# PacBot_Official_Schematic_2018-2019.net
KiCad netlist of a schematic drawn in EAGLE
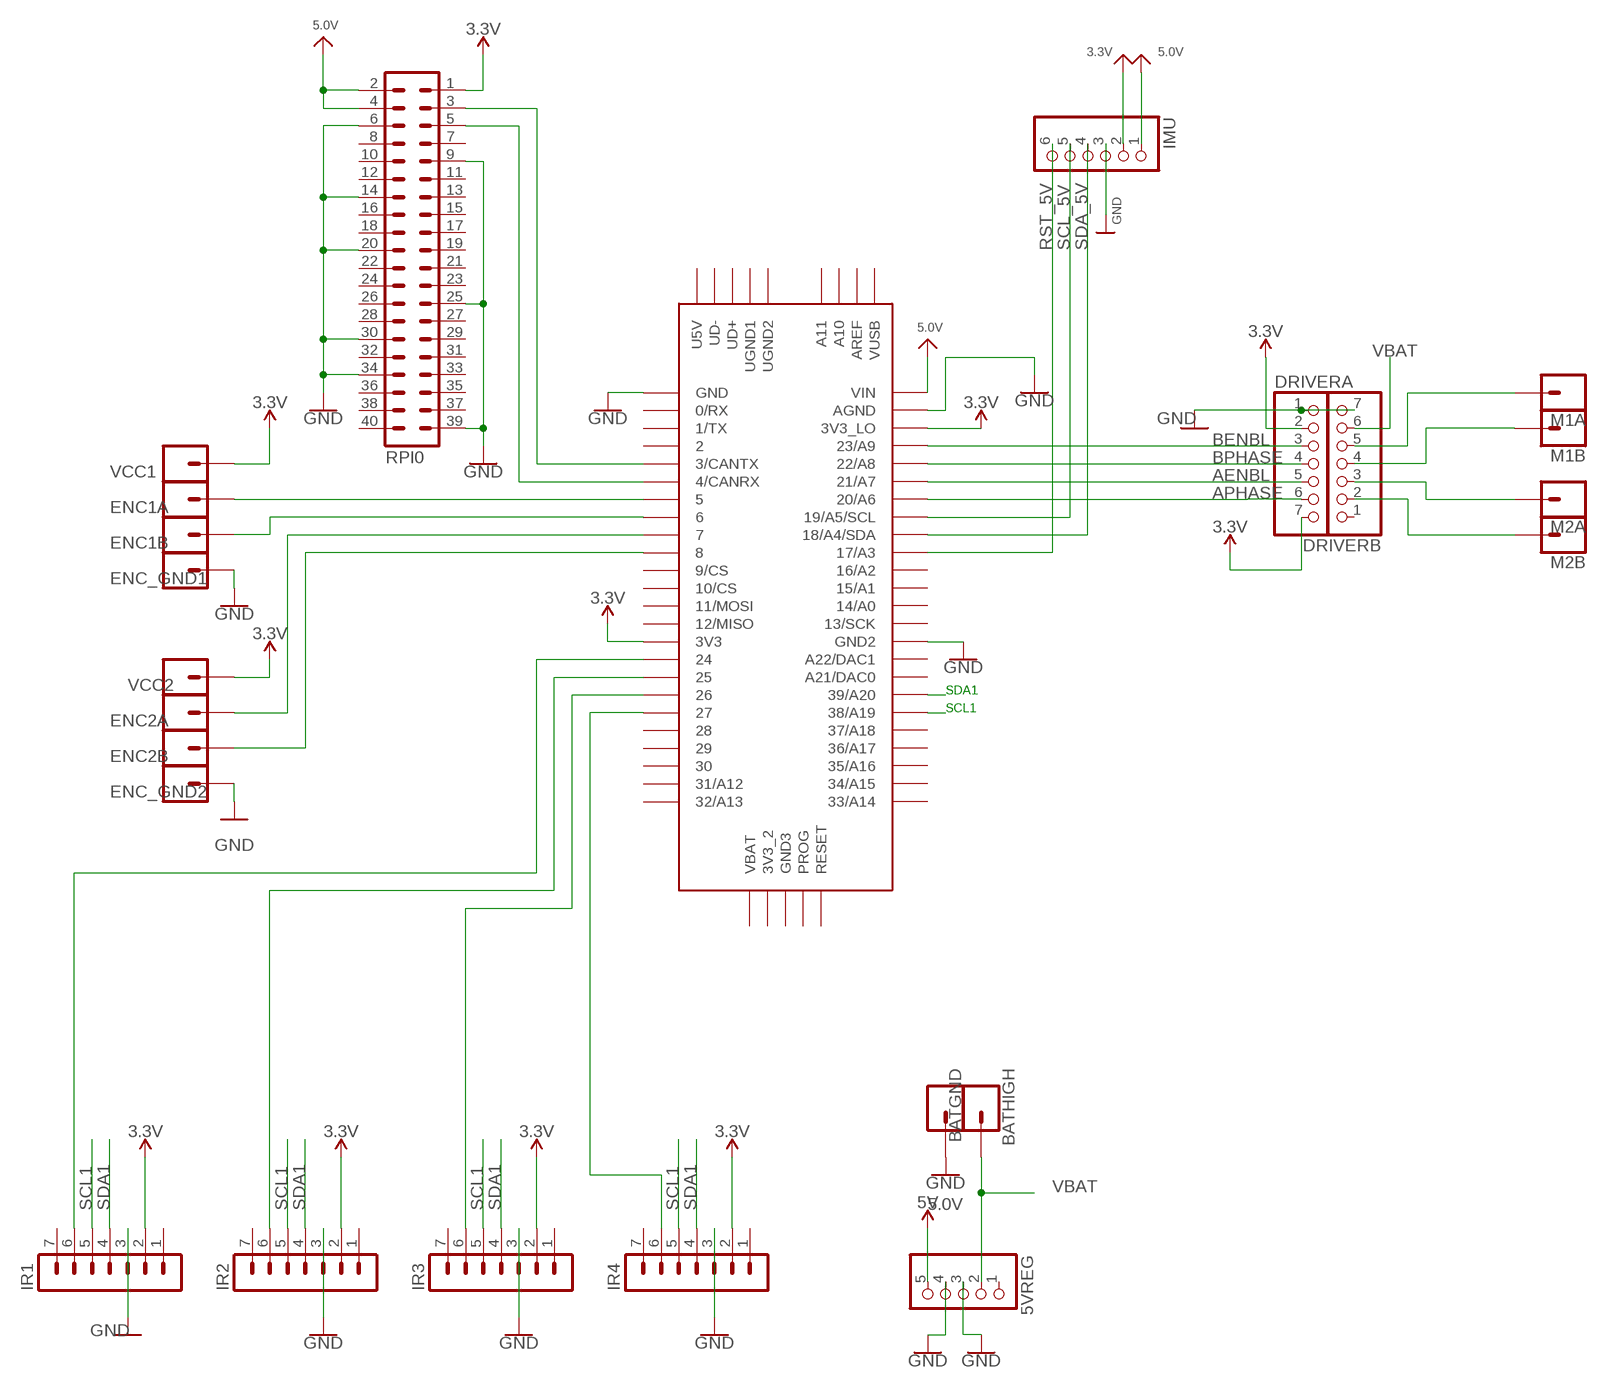
[diagram p0: schematic, sheet 1]

(export (version "E")
  (design (tool "Eeschema 10.0.6"))
  (components
    (comp (ref "5VREG")
      (value "PINHD-1X5")
      (footprint "eagle-import:1X05")
      (libsource (lib "eagle-import") (part "PINHD-1X5"))
    )
    (comp (ref "BATGND")
      (value "CONN_01")
      (footprint "eagle-import:1X01")
      (libsource (lib "eagle-import") (part "CONN_01"))
    )
    (comp (ref "BATHIGH")
      (value "CONN_01")
      (footprint "eagle-import:1X01")
      (libsource (lib "eagle-import") (part "CONN_01"))
    )
    (comp (ref "DRIVERA")
      (value "PINHD-1X7")
      (footprint "eagle-import:1X07")
      (libsource (lib "eagle-import") (part "PINHD-1X7"))
    )
    (comp (ref "DRIVERB")
      (value "PINHD-1X7")
      (footprint "eagle-import:1X07")
      (libsource (lib "eagle-import") (part "PINHD-1X7"))
    )
    (comp (ref "ENC1A")
      (value "CONN_01")
      (footprint "eagle-import:1X01")
      (libsource (lib "eagle-import") (part "CONN_01"))
    )
    (comp (ref "ENC1B")
      (value "CONN_01")
      (footprint "eagle-import:1X01")
      (libsource (lib "eagle-import") (part "CONN_01"))
    )
    (comp (ref "ENC2A")
      (value "CONN_01")
      (footprint "eagle-import:1X01")
      (libsource (lib "eagle-import") (part "CONN_01"))
    )
    (comp (ref "ENC2B")
      (value "CONN_01")
      (footprint "eagle-import:1X01")
      (libsource (lib "eagle-import") (part "CONN_01"))
    )
    (comp (ref "ENC_GND1")
      (value "CONN_01")
      (footprint "eagle-import:1X01")
      (libsource (lib "eagle-import") (part "CONN_01"))
    )
    (comp (ref "ENC_GND2")
      (value "CONN_01")
      (footprint "eagle-import:1X01")
      (libsource (lib "eagle-import") (part "CONN_01"))
    )
    (comp (ref "IMU")
      (value "HEADER-1X676MIL")
      (footprint "eagle-import:1X06_ROUND_76")
      (libsource (lib "eagle-import") (part "HEADER-1X676MIL"))
    )
    (comp (ref "IR1")
      (value "MA07-1")
      (footprint "eagle-import:MA07-1")
      (libsource (lib "eagle-import") (part "MA07-1"))
    )
    (comp (ref "IR2")
      (value "MA07-1")
      (footprint "eagle-import:MA07-1")
      (libsource (lib "eagle-import") (part "MA07-1"))
    )
    (comp (ref "IR3")
      (value "MA07-1")
      (footprint "eagle-import:MA07-1")
      (libsource (lib "eagle-import") (part "MA07-1"))
    )
    (comp (ref "IR4")
      (value "MA07-1")
      (footprint "eagle-import:MA07-1")
      (libsource (lib "eagle-import") (part "MA07-1"))
    )
    (comp (ref "M1A")
      (value "CONN_01")
      (footprint "eagle-import:1X01")
      (libsource (lib "eagle-import") (part "CONN_01"))
    )
    (comp (ref "M1B")
      (value "CONN_01")
      (footprint "eagle-import:1X01")
      (libsource (lib "eagle-import") (part "CONN_01"))
    )
    (comp (ref "M2A")
      (value "CONN_01")
      (footprint "eagle-import:1X01")
      (libsource (lib "eagle-import") (part "CONN_01"))
    )
    (comp (ref "M2B")
      (value "CONN_01")
      (footprint "eagle-import:1X01")
      (libsource (lib "eagle-import") (part "CONN_01"))
    )
    (comp (ref "RPI0")
      (value "MA20-2")
      (footprint "eagle-import:MA20-2")
      (libsource (lib "eagle-import") (part "MA20-2"))
    )
    (comp (ref "U$1")
      (value "TEENSY_3.5/3.6")
      (footprint "eagle-import:TEENSY_3.5_3.6")
      (libsource (lib "eagle-import") (part "TEENSY_3.5/3.6"))
    )
    (comp (ref "VCC1")
      (value "CONN_01")
      (footprint "eagle-import:1X01")
      (libsource (lib "eagle-import") (part "CONN_01"))
    )
    (comp (ref "VCC2")
      (value "CONN_01")
      (footprint "eagle-import:1X01")
      (libsource (lib "eagle-import") (part "CONN_01"))
    )
  )
  (nets
    (net (code "1") (name "/AENBL") (class "Default")
      (node (ref "DRIVERA") (pin "5") (pinfunction "5_5") (pintype "passive"))
      (node (ref "U$1") (pin "21/A7") (pinfunction "21/A7_21/A7") (pintype "bidirectional"))
    )
    (net (code "2") (name "/APHASE") (class "Default")
      (node (ref "DRIVERA") (pin "6") (pinfunction "6_6") (pintype "passive"))
      (node (ref "U$1") (pin "20/A6") (pinfunction "20/A6_20/A6") (pintype "bidirectional"))
    )
    (net (code "3") (name "/BENBL") (class "Default")
      (node (ref "DRIVERA") (pin "3") (pinfunction "3_3") (pintype "passive"))
      (node (ref "U$1") (pin "23/A9") (pinfunction "23/A9_23/A9") (pintype "bidirectional"))
    )
    (net (code "4") (name "/BPHASE") (class "Default")
      (node (ref "DRIVERA") (pin "4") (pinfunction "4_4") (pintype "passive"))
      (node (ref "U$1") (pin "22/A8") (pinfunction "22/A8_22/A8") (pintype "bidirectional"))
    )
    (net (code "5") (name "/RST_5V") (class "Default")
      (node (ref "IMU") (pin "6") (pinfunction "6_6") (pintype "passive"))
      (node (ref "U$1") (pin "17/A3") (pinfunction "17/A3_17/A3") (pintype "bidirectional"))
    )
    (net (code "6") (name "/SCL1") (class "Default")
      (node (ref "IR1") (pin "5") (pinfunction "5_5") (pintype "passive"))
      (node (ref "IR2") (pin "5") (pinfunction "5_5") (pintype "passive"))
      (node (ref "IR3") (pin "5") (pinfunction "5_5") (pintype "passive"))
      (node (ref "IR4") (pin "5") (pinfunction "5_5") (pintype "passive"))
      (node (ref "U$1") (pin "38/A19") (pinfunction "38/A19_38/A19") (pintype "bidirectional"))
    )
    (net (code "7") (name "/SCL_5V") (class "Default")
      (node (ref "IMU") (pin "5") (pinfunction "5_5") (pintype "passive"))
      (node (ref "U$1") (pin "19/A5/SCL") (pinfunction "19/A5/SCL_19/A5/SCL") (pintype "bidirectional"))
    )
    (net (code "8") (name "/SDA1") (class "Default")
      (node (ref "IR1") (pin "4") (pinfunction "4_4") (pintype "passive"))
      (node (ref "IR2") (pin "4") (pinfunction "4_4") (pintype "passive"))
      (node (ref "IR3") (pin "4") (pinfunction "4_4") (pintype "passive"))
      (node (ref "IR4") (pin "4") (pinfunction "4_4") (pintype "passive"))
      (node (ref "U$1") (pin "39/A20") (pinfunction "39/A20_39/A20") (pintype "bidirectional"))
    )
    (net (code "9") (name "/SDA_5V") (class "Default")
      (node (ref "IMU") (pin "4") (pinfunction "4_4") (pintype "passive"))
      (node (ref "U$1") (pin "18/A4/SDA") (pinfunction "18/A4/SDA_18/A4/SDA") (pintype "bidirectional"))
    )
    (net (code "10") (name "/VBAT") (class "Default")
      (node (ref "5VREG") (pin "2") (pinfunction "2_2") (pintype "passive"))
      (node (ref "BATHIGH") (pin "1") (pinfunction "1_1") (pintype "passive"))
      (node (ref "DRIVERB") (pin "6") (pinfunction "6_6") (pintype "passive"))
    )
    (net (code "11") (name "3.3V") (class "Default")
      (node (ref "DRIVERA") (pin "2") (pinfunction "2_2") (pintype "passive"))
      (node (ref "DRIVERA") (pin "7") (pinfunction "7_7") (pintype "passive"))
      (node (ref "IMU") (pin "2") (pinfunction "2_2") (pintype "passive"))
      (node (ref "IR1") (pin "2") (pinfunction "2_2") (pintype "passive"))
      (node (ref "IR2") (pin "2") (pinfunction "2_2") (pintype "passive"))
      (node (ref "IR3") (pin "2") (pinfunction "2_2") (pintype "passive"))
      (node (ref "IR4") (pin "2") (pinfunction "2_2") (pintype "passive"))
      (node (ref "RPI0") (pin "1") (pinfunction "1_1") (pintype "passive"))
      (node (ref "U$1") (pin "3V3") (pinfunction "3V3_3V3") (pintype "bidirectional"))
      (node (ref "U$1") (pin "3V3_LO") (pinfunction "3V3_LO_3V3_LO") (pintype "bidirectional"))
      (node (ref "VCC1") (pin "1") (pinfunction "1_1") (pintype "passive"))
      (node (ref "VCC2") (pin "1") (pinfunction "1_1") (pintype "passive"))
    )
    (net (code "12") (name "5.0V") (class "Default")
      (node (ref "5VREG") (pin "5") (pinfunction "5_5") (pintype "passive"))
      (node (ref "IMU") (pin "1") (pinfunction "1_1") (pintype "passive"))
      (node (ref "RPI0") (pin "2") (pinfunction "2_2") (pintype "passive"))
      (node (ref "RPI0") (pin "4") (pinfunction "4_4") (pintype "passive"))
      (node (ref "U$1") (pin "VIN") (pinfunction "VIN_VIN") (pintype "bidirectional"))
    )
    (net (code "13") (name "GND") (class "Default")
      (node (ref "5VREG") (pin "3") (pinfunction "3_3") (pintype "passive"))
      (node (ref "5VREG") (pin "4") (pinfunction "4_4") (pintype "passive"))
      (node (ref "BATGND") (pin "1") (pinfunction "1_1") (pintype "passive"))
      (node (ref "DRIVERA") (pin "1") (pinfunction "1_1") (pintype "passive"))
      (node (ref "DRIVERB") (pin "7") (pinfunction "7_7") (pintype "passive"))
      (node (ref "ENC_GND1") (pin "1") (pinfunction "1_1") (pintype "passive"))
      (node (ref "ENC_GND2") (pin "1") (pinfunction "1_1") (pintype "passive"))
      (node (ref "IMU") (pin "3") (pinfunction "3_3") (pintype "passive"))
      (node (ref "IR1") (pin "3") (pinfunction "3_3") (pintype "passive"))
      (node (ref "IR2") (pin "3") (pinfunction "3_3") (pintype "passive"))
      (node (ref "IR3") (pin "3") (pinfunction "3_3") (pintype "passive"))
      (node (ref "IR4") (pin "3") (pinfunction "3_3") (pintype "passive"))
      (node (ref "RPI0") (pin "14") (pinfunction "14_14") (pintype "passive"))
      (node (ref "RPI0") (pin "20") (pinfunction "20_20") (pintype "passive"))
      (node (ref "RPI0") (pin "25") (pinfunction "25_25") (pintype "passive"))
      (node (ref "RPI0") (pin "30") (pinfunction "30_30") (pintype "passive"))
      (node (ref "RPI0") (pin "34") (pinfunction "34_34") (pintype "passive"))
      (node (ref "RPI0") (pin "39") (pinfunction "39_39") (pintype "passive"))
      (node (ref "RPI0") (pin "6") (pinfunction "6_6") (pintype "passive"))
      (node (ref "RPI0") (pin "9") (pinfunction "9_9") (pintype "passive"))
      (node (ref "U$1") (pin "AGND") (pinfunction "AGND_AGND") (pintype "bidirectional"))
      (node (ref "U$1") (pin "GND") (pinfunction "GND_GND") (pintype "bidirectional"))
      (node (ref "U$1") (pin "GND2") (pinfunction "GND2_GND2") (pintype "bidirectional"))
    )
    (net (code "14") (name "Net-(DRIVERB-Pad2)") (class "Default")
      (node (ref "DRIVERB") (pin "2") (pinfunction "2_2") (pintype "passive"))
      (node (ref "M2B") (pin "1") (pinfunction "1_1") (pintype "passive"))
    )
    (net (code "15") (name "Net-(DRIVERB-Pad3)") (class "Default")
      (node (ref "DRIVERB") (pin "3") (pinfunction "3_3") (pintype "passive"))
      (node (ref "M2A") (pin "1") (pinfunction "1_1") (pintype "passive"))
    )
    (net (code "16") (name "Net-(DRIVERB-Pad4)") (class "Default")
      (node (ref "DRIVERB") (pin "4") (pinfunction "4_4") (pintype "passive"))
      (node (ref "M1B") (pin "1") (pinfunction "1_1") (pintype "passive"))
    )
    (net (code "17") (name "Net-(DRIVERB-Pad5)") (class "Default")
      (node (ref "DRIVERB") (pin "5") (pinfunction "5_5") (pintype "passive"))
      (node (ref "M1A") (pin "1") (pinfunction "1_1") (pintype "passive"))
    )
    (net (code "18") (name "Net-(ENC1A-Pad1)") (class "Default")
      (node (ref "ENC1A") (pin "1") (pinfunction "1_1") (pintype "passive"))
      (node (ref "U$1") (pin "5") (pinfunction "5_5") (pintype "bidirectional"))
    )
    (net (code "19") (name "Net-(ENC1B-Pad1)") (class "Default")
      (node (ref "ENC1B") (pin "1") (pinfunction "1_1") (pintype "passive"))
      (node (ref "U$1") (pin "6") (pinfunction "6_6") (pintype "bidirectional"))
    )
    (net (code "20") (name "Net-(ENC2A-Pad1)") (class "Default")
      (node (ref "ENC2A") (pin "1") (pinfunction "1_1") (pintype "passive"))
      (node (ref "U$1") (pin "7") (pinfunction "7_7") (pintype "bidirectional"))
    )
    (net (code "21") (name "Net-(ENC2B-Pad1)") (class "Default")
      (node (ref "ENC2B") (pin "1") (pinfunction "1_1") (pintype "passive"))
      (node (ref "U$1") (pin "8") (pinfunction "8_8") (pintype "bidirectional"))
    )
    (net (code "22") (name "Net-(IR1-Pad6)") (class "Default")
      (node (ref "IR1") (pin "6") (pinfunction "6_6") (pintype "passive"))
      (node (ref "U$1") (pin "24") (pinfunction "24_24") (pintype "bidirectional"))
    )
    (net (code "23") (name "Net-(IR2-Pad6)") (class "Default")
      (node (ref "IR2") (pin "6") (pinfunction "6_6") (pintype "passive"))
      (node (ref "U$1") (pin "25") (pinfunction "25_25") (pintype "bidirectional"))
    )
    (net (code "24") (name "Net-(IR3-Pad6)") (class "Default")
      (node (ref "IR3") (pin "6") (pinfunction "6_6") (pintype "passive"))
      (node (ref "U$1") (pin "26") (pinfunction "26_26") (pintype "bidirectional"))
    )
    (net (code "25") (name "Net-(IR4-Pad6)") (class "Default")
      (node (ref "IR4") (pin "6") (pinfunction "6_6") (pintype "passive"))
      (node (ref "U$1") (pin "27") (pinfunction "27_27") (pintype "bidirectional"))
    )
    (net (code "26") (name "Net-(RPI0-Pad3)") (class "Default")
      (node (ref "RPI0") (pin "3") (pinfunction "3_3") (pintype "passive"))
      (node (ref "U$1") (pin "3/CANTX") (pinfunction "3/CANTX_3/CANTX") (pintype "bidirectional"))
    )
    (net (code "27") (name "Net-(RPI0-Pad5)") (class "Default")
      (node (ref "RPI0") (pin "5") (pinfunction "5_5") (pintype "passive"))
      (node (ref "U$1") (pin "4/CANRX") (pinfunction "4/CANRX_4/CANRX") (pintype "bidirectional"))
    )
    (net (code "28") (name "unconnected-(5VREG-Pad1)") (class "Default")
      (node (ref "5VREG") (pin "1") (pinfunction "1_1") (pintype "passive"))
    )
    (net (code "29") (name "unconnected-(DRIVERB-Pad1)") (class "Default")
      (node (ref "DRIVERB") (pin "1") (pinfunction "1_1") (pintype "passive"))
    )
    (net (code "30") (name "unconnected-(IR1-Pad1)") (class "Default")
      (node (ref "IR1") (pin "1") (pinfunction "1_1") (pintype "passive"))
    )
    (net (code "31") (name "unconnected-(IR1-Pad7)") (class "Default")
      (node (ref "IR1") (pin "7") (pinfunction "7_7") (pintype "passive"))
    )
    (net (code "32") (name "unconnected-(IR2-Pad1)") (class "Default")
      (node (ref "IR2") (pin "1") (pinfunction "1_1") (pintype "passive"))
    )
    (net (code "33") (name "unconnected-(IR2-Pad7)") (class "Default")
      (node (ref "IR2") (pin "7") (pinfunction "7_7") (pintype "passive"))
    )
    (net (code "34") (name "unconnected-(IR3-Pad1)") (class "Default")
      (node (ref "IR3") (pin "1") (pinfunction "1_1") (pintype "passive"))
    )
    (net (code "35") (name "unconnected-(IR3-Pad7)") (class "Default")
      (node (ref "IR3") (pin "7") (pinfunction "7_7") (pintype "passive"))
    )
    (net (code "36") (name "unconnected-(IR4-Pad1)") (class "Default")
      (node (ref "IR4") (pin "1") (pinfunction "1_1") (pintype "passive"))
    )
    (net (code "37") (name "unconnected-(IR4-Pad7)") (class "Default")
      (node (ref "IR4") (pin "7") (pinfunction "7_7") (pintype "passive"))
    )
    (net (code "38") (name "unconnected-(RPI0-Pad7)") (class "Default")
      (node (ref "RPI0") (pin "7") (pinfunction "7_7") (pintype "passive"))
    )
    (net (code "39") (name "unconnected-(RPI0-Pad8)") (class "Default")
      (node (ref "RPI0") (pin "8") (pinfunction "8_8") (pintype "passive"))
    )
    (net (code "40") (name "unconnected-(RPI0-Pad10)") (class "Default")
      (node (ref "RPI0") (pin "10") (pinfunction "10_10") (pintype "passive"))
    )
    (net (code "41") (name "unconnected-(RPI0-Pad11)") (class "Default")
      (node (ref "RPI0") (pin "11") (pinfunction "11_11") (pintype "passive"))
    )
    (net (code "42") (name "unconnected-(RPI0-Pad12)") (class "Default")
      (node (ref "RPI0") (pin "12") (pinfunction "12_12") (pintype "passive"))
    )
    (net (code "43") (name "unconnected-(RPI0-Pad13)") (class "Default")
      (node (ref "RPI0") (pin "13") (pinfunction "13_13") (pintype "passive"))
    )
    (net (code "44") (name "unconnected-(RPI0-Pad15)") (class "Default")
      (node (ref "RPI0") (pin "15") (pinfunction "15_15") (pintype "passive"))
    )
    (net (code "45") (name "unconnected-(RPI0-Pad16)") (class "Default")
      (node (ref "RPI0") (pin "16") (pinfunction "16_16") (pintype "passive"))
    )
    (net (code "46") (name "unconnected-(RPI0-Pad17)") (class "Default")
      (node (ref "RPI0") (pin "17") (pinfunction "17_17") (pintype "passive"))
    )
    (net (code "47") (name "unconnected-(RPI0-Pad18)") (class "Default")
      (node (ref "RPI0") (pin "18") (pinfunction "18_18") (pintype "passive"))
    )
    (net (code "48") (name "unconnected-(RPI0-Pad19)") (class "Default")
      (node (ref "RPI0") (pin "19") (pinfunction "19_19") (pintype "passive"))
    )
    (net (code "49") (name "unconnected-(RPI0-Pad21)") (class "Default")
      (node (ref "RPI0") (pin "21") (pinfunction "21_21") (pintype "passive"))
    )
    (net (code "50") (name "unconnected-(RPI0-Pad22)") (class "Default")
      (node (ref "RPI0") (pin "22") (pinfunction "22_22") (pintype "passive"))
    )
    (net (code "51") (name "unconnected-(RPI0-Pad23)") (class "Default")
      (node (ref "RPI0") (pin "23") (pinfunction "23_23") (pintype "passive"))
    )
    (net (code "52") (name "unconnected-(RPI0-Pad24)") (class "Default")
      (node (ref "RPI0") (pin "24") (pinfunction "24_24") (pintype "passive"))
    )
    (net (code "53") (name "unconnected-(RPI0-Pad26)") (class "Default")
      (node (ref "RPI0") (pin "26") (pinfunction "26_26") (pintype "passive"))
    )
    (net (code "54") (name "unconnected-(RPI0-Pad27)") (class "Default")
      (node (ref "RPI0") (pin "27") (pinfunction "27_27") (pintype "passive"))
    )
    (net (code "55") (name "unconnected-(RPI0-Pad28)") (class "Default")
      (node (ref "RPI0") (pin "28") (pinfunction "28_28") (pintype "passive"))
    )
    (net (code "56") (name "unconnected-(RPI0-Pad29)") (class "Default")
      (node (ref "RPI0") (pin "29") (pinfunction "29_29") (pintype "passive"))
    )
    (net (code "57") (name "unconnected-(RPI0-Pad31)") (class "Default")
      (node (ref "RPI0") (pin "31") (pinfunction "31_31") (pintype "passive"))
    )
    (net (code "58") (name "unconnected-(RPI0-Pad32)") (class "Default")
      (node (ref "RPI0") (pin "32") (pinfunction "32_32") (pintype "passive"))
    )
    (net (code "59") (name "unconnected-(RPI0-Pad33)") (class "Default")
      (node (ref "RPI0") (pin "33") (pinfunction "33_33") (pintype "passive"))
    )
    (net (code "60") (name "unconnected-(RPI0-Pad35)") (class "Default")
      (node (ref "RPI0") (pin "35") (pinfunction "35_35") (pintype "passive"))
    )
    (net (code "61") (name "unconnected-(RPI0-Pad36)") (class "Default")
      (node (ref "RPI0") (pin "36") (pinfunction "36_36") (pintype "passive"))
    )
    (net (code "62") (name "unconnected-(RPI0-Pad37)") (class "Default")
      (node (ref "RPI0") (pin "37") (pinfunction "37_37") (pintype "passive"))
    )
    (net (code "63") (name "unconnected-(RPI0-Pad38)") (class "Default")
      (node (ref "RPI0") (pin "38") (pinfunction "38_38") (pintype "passive"))
    )
    (net (code "64") (name "unconnected-(RPI0-Pad40)") (class "Default")
      (node (ref "RPI0") (pin "40") (pinfunction "40_40") (pintype "passive"))
    )
    (net (code "65") (name "unconnected-(U$1-A21{slash}DAC0-Pad21{slash}DAC0)") (class "Default")
      (node (ref "U$1") (pin "21/DAC0") (pinfunction "A21/DAC0_21/DAC0") (pintype "bidirectional"))
    )
    (net (code "66") (name "unconnected-(U$1-Pad0{slash}RX)") (class "Default")
      (node (ref "U$1") (pin "0/RX") (pinfunction "0/RX_0/RX") (pintype "bidirectional"))
    )
    (net (code "67") (name "unconnected-(U$1-Pad1{slash}TX)") (class "Default")
      (node (ref "U$1") (pin "1/TX") (pinfunction "1/TX_1/TX") (pintype "bidirectional"))
    )
    (net (code "68") (name "unconnected-(U$1-Pad2)") (class "Default")
      (node (ref "U$1") (pin "2") (pinfunction "2_2") (pintype "bidirectional"))
    )
    (net (code "69") (name "unconnected-(U$1-Pad3V3_2)") (class "Default")
      (node (ref "U$1") (pin "3V3_2") (pinfunction "3V3_2_3V3_2") (pintype "bidirectional"))
    )
    (net (code "70") (name "unconnected-(U$1-Pad9{slash}CS)") (class "Default")
      (node (ref "U$1") (pin "9/CS") (pinfunction "9/CS_9/CS") (pintype "bidirectional"))
    )
    (net (code "71") (name "unconnected-(U$1-Pad10{slash}CS)") (class "Default")
      (node (ref "U$1") (pin "10/CS") (pinfunction "10/CS_10/CS") (pintype "bidirectional"))
    )
    (net (code "72") (name "unconnected-(U$1-Pad11{slash}MOSI)") (class "Default")
      (node (ref "U$1") (pin "11/MOSI") (pinfunction "11/MOSI_11/MOSI") (pintype "bidirectional"))
    )
    (net (code "73") (name "unconnected-(U$1-Pad12{slash}MISO)") (class "Default")
      (node (ref "U$1") (pin "12/MISO") (pinfunction "12/MISO_12/MISO") (pintype "bidirectional"))
    )
    (net (code "74") (name "unconnected-(U$1-Pad13{slash}SCK)") (class "Default")
      (node (ref "U$1") (pin "13/SCK") (pinfunction "13/SCK_13/SCK") (pintype "bidirectional"))
    )
    (net (code "75") (name "unconnected-(U$1-Pad14{slash}A0)") (class "Default")
      (node (ref "U$1") (pin "14/A0") (pinfunction "14/A0_14/A0") (pintype "bidirectional"))
    )
    (net (code "76") (name "unconnected-(U$1-Pad15{slash}A1)") (class "Default")
      (node (ref "U$1") (pin "15/A1") (pinfunction "15/A1_15/A1") (pintype "bidirectional"))
    )
    (net (code "77") (name "unconnected-(U$1-Pad16{slash}A2)") (class "Default")
      (node (ref "U$1") (pin "16/A2") (pinfunction "16/A2_16/A2") (pintype "bidirectional"))
    )
    (net (code "78") (name "unconnected-(U$1-Pad28)") (class "Default")
      (node (ref "U$1") (pin "28") (pinfunction "28_28") (pintype "bidirectional"))
    )
    (net (code "79") (name "unconnected-(U$1-Pad29)") (class "Default")
      (node (ref "U$1") (pin "29") (pinfunction "29_29") (pintype "bidirectional"))
    )
    (net (code "80") (name "unconnected-(U$1-Pad30)") (class "Default")
      (node (ref "U$1") (pin "30") (pinfunction "30_30") (pintype "bidirectional"))
    )
    (net (code "81") (name "unconnected-(U$1-Pad31{slash}A12)") (class "Default")
      (node (ref "U$1") (pin "31/A12") (pinfunction "31/A12_31/A12") (pintype "bidirectional"))
    )
    (net (code "82") (name "unconnected-(U$1-Pad32{slash}A13)") (class "Default")
      (node (ref "U$1") (pin "32/A13") (pinfunction "32/A13_32/A13") (pintype "bidirectional"))
    )
    (net (code "83") (name "unconnected-(U$1-Pad33{slash}A14)") (class "Default")
      (node (ref "U$1") (pin "33/A14") (pinfunction "33/A14_33/A14") (pintype "bidirectional"))
    )
    (net (code "84") (name "unconnected-(U$1-Pad34{slash}A15)") (class "Default")
      (node (ref "U$1") (pin "34/A15") (pinfunction "34/A15_34/A15") (pintype "bidirectional"))
    )
    (net (code "85") (name "unconnected-(U$1-Pad35{slash}A16)") (class "Default")
      (node (ref "U$1") (pin "35/A16") (pinfunction "35/A16_35/A16") (pintype "bidirectional"))
    )
    (net (code "86") (name "unconnected-(U$1-Pad36{slash}A17)") (class "Default")
      (node (ref "U$1") (pin "36/A17") (pinfunction "36/A17_36/A17") (pintype "bidirectional"))
    )
    (net (code "87") (name "unconnected-(U$1-Pad37{slash}A18)") (class "Default")
      (node (ref "U$1") (pin "37/A18") (pinfunction "37/A18_37/A18") (pintype "bidirectional"))
    )
    (net (code "88") (name "unconnected-(U$1-PadA10)") (class "Default")
      (node (ref "U$1") (pin "A10") (pinfunction "A10_A10") (pintype "bidirectional"))
    )
    (net (code "89") (name "unconnected-(U$1-PadA11)") (class "Default")
      (node (ref "U$1") (pin "A11") (pinfunction "A11_A11") (pintype "bidirectional"))
    )
    (net (code "90") (name "unconnected-(U$1-PadA22{slash}DAC1)") (class "Default")
      (node (ref "U$1") (pin "A22/DAC1") (pinfunction "A22/DAC1_A22/DAC1") (pintype "bidirectional"))
    )
    (net (code "91") (name "unconnected-(U$1-PadAREF)") (class "Default")
      (node (ref "U$1") (pin "AREF") (pinfunction "AREF_AREF") (pintype "bidirectional"))
    )
    (net (code "92") (name "unconnected-(U$1-PadGND3)") (class "Default")
      (node (ref "U$1") (pin "GND3") (pinfunction "GND3_GND3") (pintype "bidirectional"))
    )
    (net (code "93") (name "unconnected-(U$1-PadPROG)") (class "Default")
      (node (ref "U$1") (pin "PROG") (pinfunction "PROG_PROG") (pintype "bidirectional"))
    )
    (net (code "94") (name "unconnected-(U$1-PadRESET)") (class "Default")
      (node (ref "U$1") (pin "RESET") (pinfunction "RESET_RESET") (pintype "bidirectional"))
    )
    (net (code "95") (name "unconnected-(U$1-PadU5V)") (class "Default")
      (node (ref "U$1") (pin "U5V") (pinfunction "U5V_U5V") (pintype "bidirectional"))
    )
    (net (code "96") (name "unconnected-(U$1-PadUD+)") (class "Default")
      (node (ref "U$1") (pin "UD+") (pinfunction "UD+_UD+") (pintype "bidirectional"))
    )
    (net (code "97") (name "unconnected-(U$1-PadUD-)") (class "Default")
      (node (ref "U$1") (pin "UD-") (pinfunction "UD-_UD-") (pintype "bidirectional"))
    )
    (net (code "98") (name "unconnected-(U$1-PadUGND1)") (class "Default")
      (node (ref "U$1") (pin "UGND1") (pinfunction "UGND1_UGND1") (pintype "bidirectional"))
    )
    (net (code "99") (name "unconnected-(U$1-PadUGND2)") (class "Default")
      (node (ref "U$1") (pin "UGND2") (pinfunction "UGND2_UGND2") (pintype "bidirectional"))
    )
    (net (code "100") (name "unconnected-(U$1-PadVBAT)") (class "Default")
      (node (ref "U$1") (pin "VBAT") (pinfunction "VBAT_VBAT") (pintype "bidirectional"))
    )
    (net (code "101") (name "unconnected-(U$1-PadVUSB)") (class "Default")
      (node (ref "U$1") (pin "VUSB") (pinfunction "VUSB_VUSB") (pintype "bidirectional"))
    )
  )
)
